# Mosfet_Driver.net
KiCad netlist of a schematic drawn in Altium Designer
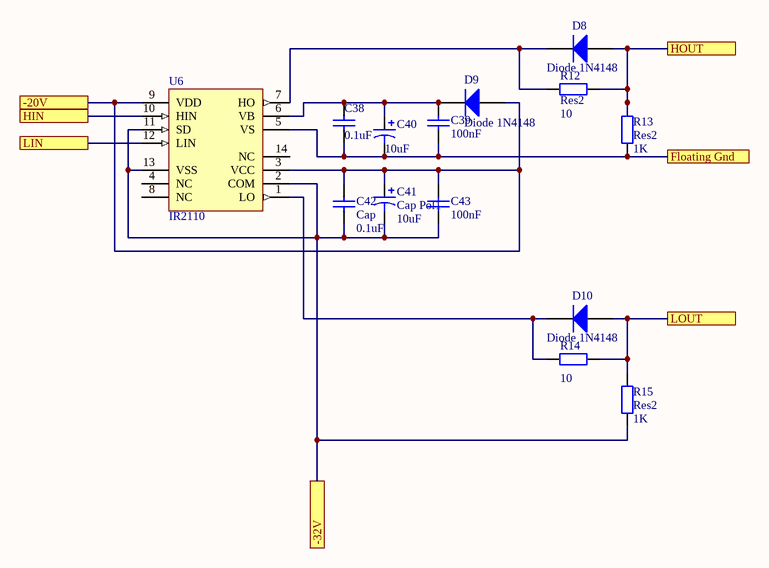
[diagram p0: Mosfet Driver.SchDoc]

(export (version "E")
  (design (tool "Eeschema 10.0.6"))
  (components
    (comp (ref "C38")
      (value "0.1uF")
      (footprint "CAP DISCO 200mil")
      (description "Capacitor")
      (fields (field (name "Comment") "Cap") (field (name "PUBLISHER") "Altium Limited"))
      (libsource (lib "Miscellaneous Devices") (part "Cap"))
    )
    (comp (ref "C39")
      (value "Cap Ceramico Disco")
      (footprint "RAD-0.3")
      (description "Capacitor Ceramico de Insercion")
      (fields (field (name "VALOR") "100nF"))
      (libsource (lib "RUF-Dispositivos-Grales") (part "Cap Ceramico Disco"))
    )
    (comp (ref "C40")
      (value "10uF")
      (footprint "CAPR D250 H450 R100 mil")
      (description "Polarized Capacitor (Radial)")
      (fields (field (name "Comment") "Cap Pol1") (field (name "PUBLISHER") "Altium Limited"))
      (libsource (lib "Miscellaneous Devices") (part "Cap Pol1"))
    )
    (comp (ref "C41")
      (value "Cap Pol1")
      (footprint "CAPR D250 H450 R100 mil")
      (description "Polarized Capacitor (Radial)")
      (fields (field (name "ALTIUM_VALUE") "10uF") (field (name "PUBLISHER") "Altium Limited"))
      (libsource (lib "Miscellaneous Devices") (part "Cap Pol1"))
    )
    (comp (ref "C42")
      (value "Cap")
      (footprint "CAP DISCO 200mil")
      (description "Capacitor")
      (fields (field (name "ALTIUM_VALUE") "0.1uF") (field (name "PUBLISHER") "Altium Limited"))
      (libsource (lib "Miscellaneous Devices") (part "Cap"))
    )
    (comp (ref "C43")
      (value "Cap Ceramico Disco")
      (footprint "RAD-0.3")
      (description "Capacitor Ceramico de Insercion")
      (fields (field (name "VALOR") "100nF"))
      (libsource (lib "RUF-Dispositivos-Grales") (part "Cap Ceramico Disco"))
    )
    (comp (ref "D8")
      (value "Diode 1N4148")
      (footprint "SOD323-F")
      (description "High Conductance Fast Diode")
      (fields (field (name "PUBLISHER") "Altium Limited"))
      (libsource (lib "Miscellaneous Devices") (part "Diode 1N4148"))
    )
    (comp (ref "D9")
      (value "Diode 1N4148")
      (footprint "SOD323-F")
      (description "High Conductance Fast Diode")
      (fields (field (name "PUBLISHER") "Altium Limited"))
      (libsource (lib "Miscellaneous Devices") (part "Diode 1N4148"))
    )
    (comp (ref "D10")
      (value "Diode 1N4148")
      (footprint "SOD323-F")
      (description "High Conductance Fast Diode")
      (fields (field (name "PUBLISHER") "Altium Limited"))
      (libsource (lib "Miscellaneous Devices") (part "Diode 1N4148"))
    )
    (comp (ref "R12")
      (value "Res2")
      (footprint "1206 resistor")
      (description "Resistor")
      (fields (field (name "ALTIUM_VALUE") "10") (field (name "PUBLISHER") "Altium Limited"))
      (libsource (lib "Miscellaneous Devices") (part "Res2"))
    )
    (comp (ref "R13")
      (value "Res2")
      (footprint "1206 resistor")
      (description "Resistor")
      (fields (field (name "ALTIUM_VALUE") "1K") (field (name "PUBLISHER") "Altium Limited"))
      (libsource (lib "") (part "Res2_2"))
    )
    (comp (ref "R14")
      (value "10")
      (footprint "1206 resistor")
      (description "Resistor")
      (fields (field (name "Comment") "Res2") (field (name "PUBLISHER") "Altium Limited"))
      (libsource (lib "") (part "Res2_1"))
    )
    (comp (ref "R15")
      (value "Res2")
      (footprint "1206 resistor")
      (description "Resistor")
      (fields (field (name "ALTIUM_VALUE") "1K") (field (name "PUBLISHER") "Altium Limited"))
      (libsource (lib "") (part "Res2_3"))
    )
    (comp (ref "U6")
      (value "IR2110")
      (footprint "PDIP14")
      (description "High and Low Side Driver")
      (fields (field (name "PUBLISHER") "Altium Limited"))
      (libsource (lib "IR Interface Bridge Driver") (part "IR2110"))
    )
  )
  (nets
    (net (code "1") (name "/-20V") (class "Default")
      (node (ref "C41") (pin "1") (pinfunction "1_1") (pintype "passive"))
      (node (ref "C42") (pin "2") (pinfunction "2_2") (pintype "passive"))
      (node (ref "C43") (pin "2") (pinfunction "2_2") (pintype "passive"))
      (node (ref "D9") (pin "1") (pinfunction "A_1") (pintype "passive"))
      (node (ref "U6") (pin "3") (pinfunction "VCC_3") (pintype "power_in"))
      (node (ref "U6") (pin "9") (pinfunction "VDD_9") (pintype "power_in"))
    )
    (net (code "2") (name "/-32V") (class "Default")
      (node (ref "C41") (pin "2") (pinfunction "2_2") (pintype "passive"))
      (node (ref "C42") (pin "1") (pinfunction "1_1") (pintype "passive"))
      (node (ref "C43") (pin "1") (pinfunction "1_1") (pintype "passive"))
      (node (ref "R15") (pin "2") (pinfunction "2_2") (pintype "passive"))
      (node (ref "U6") (pin "11") (pinfunction "SD_11") (pintype "input"))
      (node (ref "U6") (pin "13") (pinfunction "VSS_13") (pintype "power_in"))
      (node (ref "U6") (pin "2") (pinfunction "COM_2") (pintype "power_in"))
    )
    (net (code "3") (name "/Floating Gnd") (class "Default")
      (node (ref "C38") (pin "1") (pinfunction "1_1") (pintype "passive"))
      (node (ref "C39") (pin "1") (pinfunction "1_1") (pintype "passive"))
      (node (ref "C40") (pin "2") (pinfunction "2_2") (pintype "passive"))
      (node (ref "R13") (pin "1") (pinfunction "1_1") (pintype "passive"))
      (node (ref "U6") (pin "5") (pinfunction "VS_5") (pintype "power_in"))
    )
    (net (code "4") (name "/HIN") (class "Default")
      (node (ref "U6") (pin "10") (pinfunction "HIN_10") (pintype "input"))
    )
    (net (code "5") (name "/HOUT") (class "Default")
      (node (ref "D8") (pin "1") (pinfunction "A_1") (pintype "passive"))
      (node (ref "R12") (pin "2") (pinfunction "2_2") (pintype "passive"))
      (node (ref "R13") (pin "2") (pinfunction "2_2") (pintype "passive"))
    )
    (net (code "6") (name "/LIN") (class "Default")
      (node (ref "U6") (pin "12") (pinfunction "LIN_12") (pintype "input"))
    )
    (net (code "7") (name "/LOUT") (class "Default")
      (node (ref "D10") (pin "1") (pinfunction "A_1") (pintype "passive"))
      (node (ref "R14") (pin "1") (pinfunction "1_1") (pintype "passive"))
      (node (ref "R15") (pin "1") (pinfunction "1_1") (pintype "passive"))
    )
    (net (code "8") (name "Net-(D8-K)") (class "Default")
      (node (ref "D8") (pin "2") (pinfunction "K_2") (pintype "passive"))
      (node (ref "R12") (pin "1") (pinfunction "1_1") (pintype "passive"))
      (node (ref "U6") (pin "7") (pinfunction "HO_7") (pintype "output"))
    )
    (net (code "9") (name "Net-(D9-K)") (class "Default")
      (node (ref "C38") (pin "2") (pinfunction "2_2") (pintype "passive"))
      (node (ref "C39") (pin "2") (pinfunction "2_2") (pintype "passive"))
      (node (ref "C40") (pin "1") (pinfunction "1_1") (pintype "passive"))
      (node (ref "D9") (pin "2") (pinfunction "K_2") (pintype "passive"))
      (node (ref "U6") (pin "6") (pinfunction "VB_6") (pintype "power_in"))
    )
    (net (code "10") (name "Net-(D10-K)") (class "Default")
      (node (ref "D10") (pin "2") (pinfunction "K_2") (pintype "passive"))
      (node (ref "R14") (pin "2") (pinfunction "2_2") (pintype "passive"))
      (node (ref "U6") (pin "1") (pinfunction "LO_1") (pintype "output"))
    )
    (net (code "11") (name "unconnected-(U6-NC-Pad4)") (class "Default")
      (node (ref "U6") (pin "4") (pinfunction "NC_4") (pintype "passive"))
    )
    (net (code "12") (name "unconnected-(U6-NC-Pad8)") (class "Default")
      (node (ref "U6") (pin "8") (pinfunction "NC_8") (pintype "passive"))
    )
    (net (code "13") (name "unconnected-(U6-NC-Pad14)") (class "Default")
      (node (ref "U6") (pin "14") (pinfunction "NC_14") (pintype "passive"))
    )
  )
)
